# ospi152.net
KiCad netlist of a schematic drawn in EAGLE
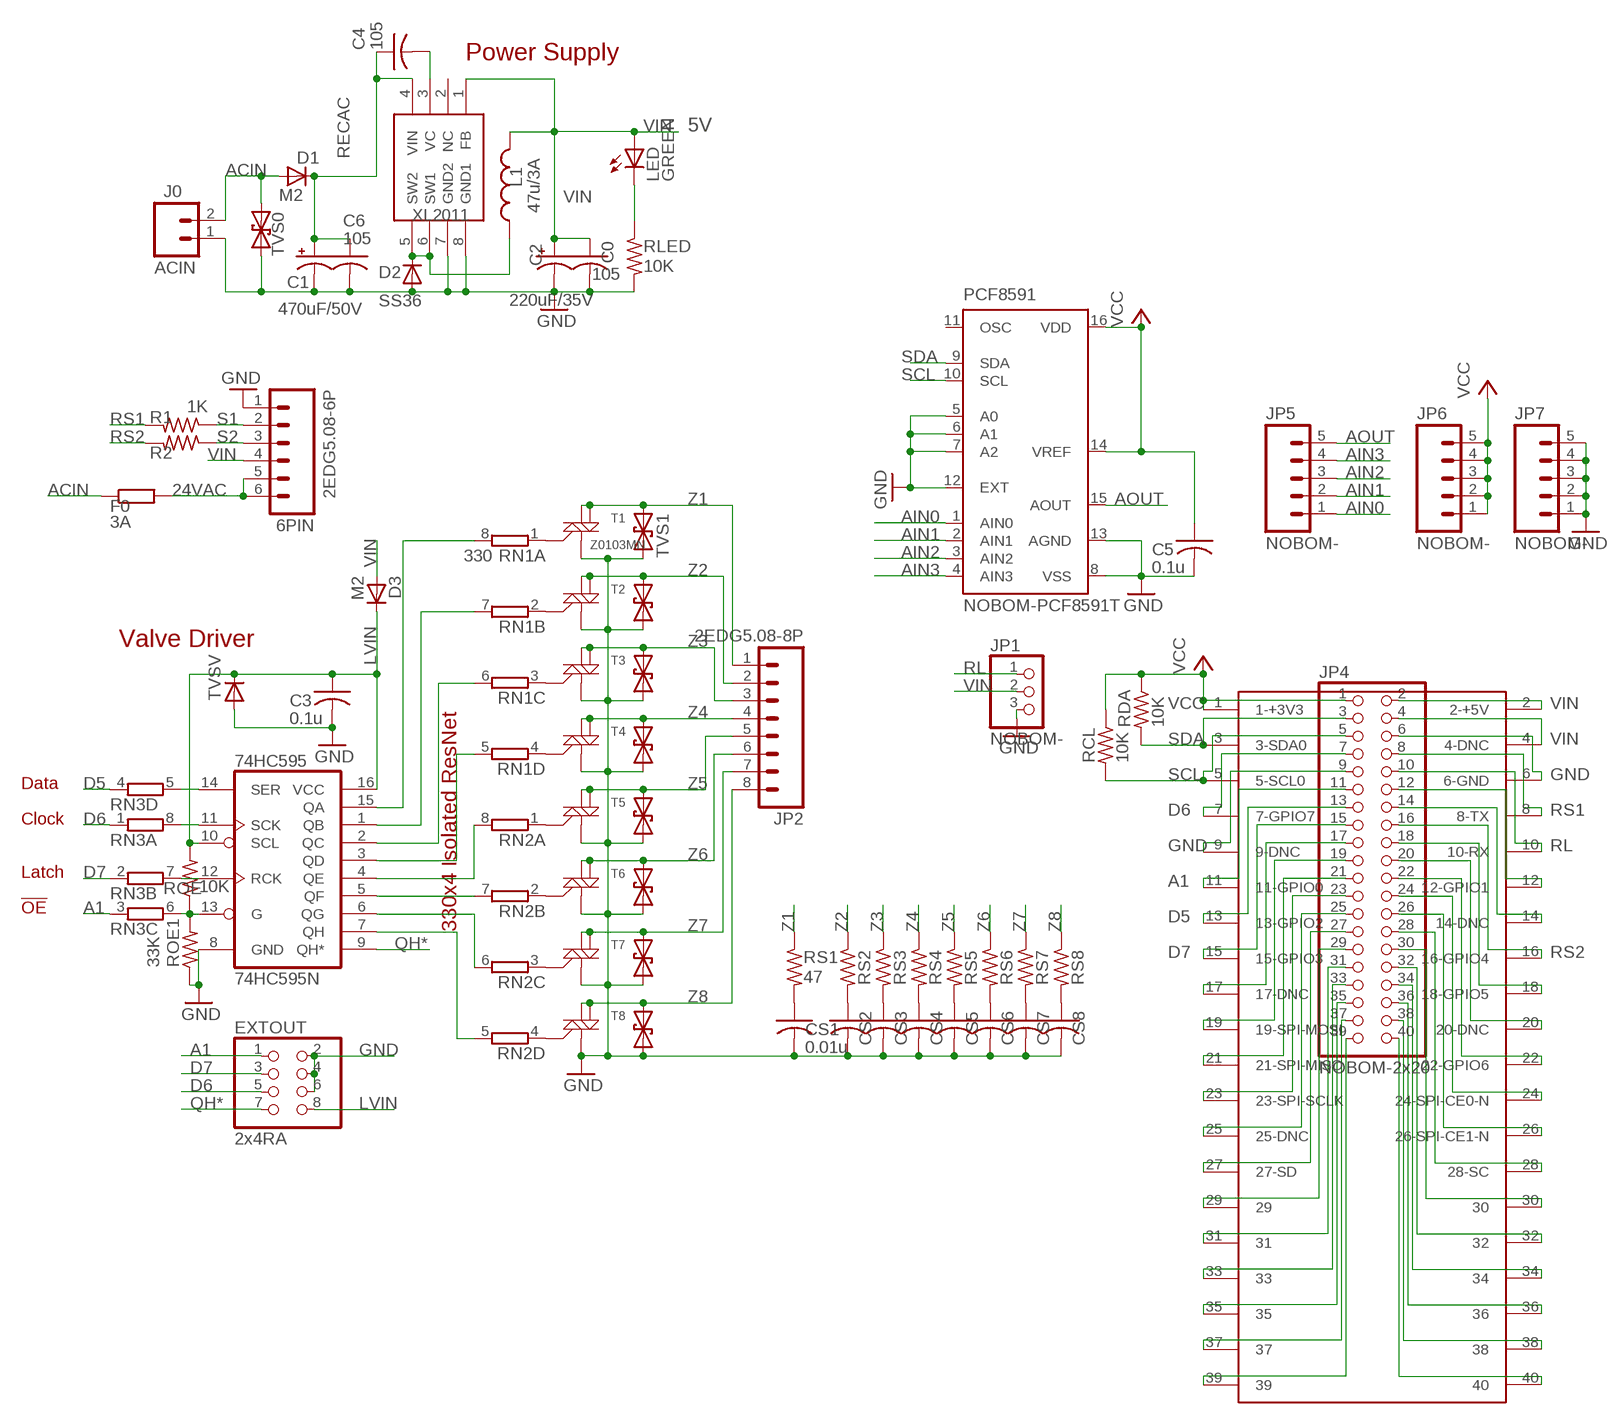
[diagram p0: schematic, sheet 1]

(export (version "E")
  (design (tool "Eeschema 10.0.6"))
  (components
    (comp (ref "6PIN")
      (value "2EDG5.08-6P")
      (footprint "eagle-import:SCREWTERMINAL-5MM-6")
      (libsource (lib "eagle-import") (part "M065MM"))
    )
    (comp (ref "74HC595")
      (value "74HC595N")
      (footprint "eagle-import:SO16")
      (libsource (lib "eagle-import") (part "74595DLS"))
    )
    (comp (ref "C0")
      (value "105")
      (footprint "eagle-import:C0603K")
      (libsource (lib "eagle-import") (part "C-USC0603K"))
    )
    (comp (ref "C1")
      (value "470uF/50V")
      (footprint "eagle-import:E5-10,5")
      (libsource (lib "eagle-import") (part "CPOL-USE5-10.5"))
    )
    (comp (ref "C2")
      (value "220uF/35V")
      (footprint "eagle-import:E3,5-8")
      (libsource (lib "eagle-import") (part "CPOL-USE3.5-8"))
    )
    (comp (ref "C3")
      (value "0.1u")
      (footprint "eagle-import:C0603K")
      (libsource (lib "eagle-import") (part "C-USC0603K"))
    )
    (comp (ref "C4")
      (value "105")
      (footprint "eagle-import:C0603K")
      (libsource (lib "eagle-import") (part "C-USC0603K"))
    )
    (comp (ref "C5")
      (value "0.1u")
      (footprint "eagle-import:C0603K")
      (libsource (lib "eagle-import") (part "C-USC0603K"))
    )
    (comp (ref "C6")
      (value "105")
      (footprint "eagle-import:C0603K")
      (libsource (lib "eagle-import") (part "C-USC0603K"))
    )
    (comp (ref "CS1")
      (value "0.01u")
      (footprint "eagle-import:C0603K")
      (libsource (lib "eagle-import") (part "C-USC0603K"))
    )
    (comp (ref "CS2")
      (value "0.01u")
      (footprint "eagle-import:C0603K")
      (libsource (lib "eagle-import") (part "C-USC0603K"))
    )
    (comp (ref "CS3")
      (value "0.01u")
      (footprint "eagle-import:C0603K")
      (libsource (lib "eagle-import") (part "C-USC0603K"))
    )
    (comp (ref "CS4")
      (value "0.01u")
      (footprint "eagle-import:C0603K")
      (libsource (lib "eagle-import") (part "C-USC0603K"))
    )
    (comp (ref "CS5")
      (value "0.01u")
      (footprint "eagle-import:C0603K")
      (libsource (lib "eagle-import") (part "C-USC0603K"))
    )
    (comp (ref "CS6")
      (value "0.01u")
      (footprint "eagle-import:C0603K")
      (libsource (lib "eagle-import") (part "C-USC0603K"))
    )
    (comp (ref "CS7")
      (value "0.01u")
      (footprint "eagle-import:C0603K")
      (libsource (lib "eagle-import") (part "C-USC0603K"))
    )
    (comp (ref "CS8")
      (value "0.01u")
      (footprint "eagle-import:C0603K")
      (libsource (lib "eagle-import") (part "C-USC0603K"))
    )
    (comp (ref "D1")
      (value "M2")
      (footprint "eagle-import:DO-214AC")
      (libsource (lib "eagle-import") (part "DIODE-DO-214AC"))
    )
    (comp (ref "D2")
      (value "SS36")
      (footprint "eagle-import:SMB")
      (libsource (lib "eagle-import") (part "DIODE-SMB"))
    )
    (comp (ref "D3")
      (value "M2")
      (footprint "eagle-import:DO-214AC")
      (libsource (lib "eagle-import") (part "DIODE-DO-214AC"))
    )
    (comp (ref "EXTOUT")
      (value "2x4RA")
      (footprint "eagle-import:2X04_90")
      (libsource (lib "eagle-import") (part "PINHD-2X4/90"))
    )
    (comp (ref "F0")
      (value "3A")
      (footprint "eagle-import:0207_15")
      (libsource (lib "eagle-import") (part "R-EU_0207/15"))
    )
    (comp (ref "J0")
      (value "ACIN")
      (footprint "eagle-import:SCREWTERMINAL-4MM-2-X")
      (libsource (lib "eagle-import") (part "M024MM-X"))
    )
    (comp (ref "JP1")
      (value "NOBOM-")
      (footprint "eagle-import:1X03")
      (libsource (lib "eagle-import") (part "PINHD-1X3"))
    )
    (comp (ref "JP2")
      (value "2EDG5.08-8P")
      (footprint "eagle-import:SCREWTERMINAL-5MM-8")
      (libsource (lib "eagle-import") (part "M085MM-8"))
    )
    (comp (ref "JP4")
      (value "NOBOM-2x20")
      (footprint "eagle-import:2X20")
      (libsource (lib "eagle-import") (part "PINHD-2X20"))
    )
    (comp (ref "JP5")
      (value "NOBOM-")
      (footprint "eagle-import:1X05")
      (libsource (lib "eagle-import") (part "M05PTH"))
    )
    (comp (ref "JP6")
      (value "NOBOM-")
      (footprint "eagle-import:1X05")
      (libsource (lib "eagle-import") (part "M05PTH"))
    )
    (comp (ref "JP7")
      (value "NOBOM-")
      (footprint "eagle-import:1X05")
      (libsource (lib "eagle-import") (part "M05PTH"))
    )
    (comp (ref "L1")
      (value "47u/3A")
      (footprint "eagle-import:YT1014")
      (libsource (lib "eagle-import") (part "INDUCTORYT1014"))
    )
    (comp (ref "LED")
      (value "GREEN")
      (footprint "eagle-import:CHIPLED_0805")
      (libsource (lib "eagle-import") (part "LEDCHIPLED_0805"))
    )
    (comp (ref "PCF8591")
      (value "NOBOM-PCF8591T")
      (footprint "eagle-import:SO16W")
      (fields (field (name "MPN") "PCF8591T/2,512"))
      (libsource (lib "eagle-import") (part "PCF8591T"))
    )
    (comp (ref "R1")
      (value "1K")
      (footprint "eagle-import:R0603")
      (libsource (lib "eagle-import") (part "R-US_R0603"))
    )
    (comp (ref "R2")
      (value "1K")
      (footprint "eagle-import:R0603")
      (libsource (lib "eagle-import") (part "R-US_R0603"))
    )
    (comp (ref "RCL")
      (value "10K")
      (footprint "eagle-import:R0603")
      (libsource (lib "eagle-import") (part "R-US_R0603"))
    )
    (comp (ref "RDA")
      (value "10K")
      (footprint "eagle-import:R0603")
      (libsource (lib "eagle-import") (part "R-US_R0603"))
    )
    (comp (ref "RLED")
      (value "10K")
      (footprint "eagle-import:R0603")
      (libsource (lib "eagle-import") (part "R-US_R0603"))
    )
    (comp (ref "RN1")
      (value "330")
      (footprint "eagle-import:EXB38V")
      (libsource (lib "eagle-import") (part "4R-NEXB38V"))
    )
    (comp (ref "RN2")
      (value "330")
      (footprint "eagle-import:EXB38V")
      (libsource (lib "eagle-import") (part "4R-NEXB38V"))
    )
    (comp (ref "RN3")
      (value "330")
      (footprint "eagle-import:EXB38V")
      (libsource (lib "eagle-import") (part "4R-NEXB38V"))
    )
    (comp (ref "ROE")
      (value "10K")
      (footprint "eagle-import:R0603")
      (libsource (lib "eagle-import") (part "R-US_R0603"))
    )
    (comp (ref "ROE1")
      (value "33K")
      (footprint "eagle-import:R0603")
      (libsource (lib "eagle-import") (part "R-US_R0603"))
    )
    (comp (ref "RPI")
      (value "RPIB+B+")
      (footprint "eagle-import:RPIB+")
      (libsource (lib "eagle-import") (part "RPIB+B+"))
    )
    (comp (ref "RS1")
      (value "47")
      (footprint "eagle-import:R0603")
      (libsource (lib "eagle-import") (part "R-US_R0603"))
    )
    (comp (ref "RS2")
      (value "47")
      (footprint "eagle-import:R0603")
      (libsource (lib "eagle-import") (part "R-US_R0603"))
    )
    (comp (ref "RS3")
      (value "47")
      (footprint "eagle-import:R0603")
      (libsource (lib "eagle-import") (part "R-US_R0603"))
    )
    (comp (ref "RS4")
      (value "47")
      (footprint "eagle-import:R0603")
      (libsource (lib "eagle-import") (part "R-US_R0603"))
    )
    (comp (ref "RS5")
      (value "47")
      (footprint "eagle-import:R0603")
      (libsource (lib "eagle-import") (part "R-US_R0603"))
    )
    (comp (ref "RS6")
      (value "47")
      (footprint "eagle-import:R0603")
      (libsource (lib "eagle-import") (part "R-US_R0603"))
    )
    (comp (ref "RS7")
      (value "47")
      (footprint "eagle-import:R0603")
      (libsource (lib "eagle-import") (part "R-US_R0603"))
    )
    (comp (ref "RS8")
      (value "47")
      (footprint "eagle-import:R0603")
      (libsource (lib "eagle-import") (part "R-US_R0603"))
    )
    (comp (ref "T1")
      (value "Z0103MN")
      (footprint "eagle-import:SOT223")
      (libsource (lib "eagle-import") (part "MAC97SOT223"))
    )
    (comp (ref "T2")
      (value "Z0103MN")
      (footprint "eagle-import:SOT223")
      (libsource (lib "eagle-import") (part "MAC97SOT223"))
    )
    (comp (ref "T3")
      (value "Z0103MN")
      (footprint "eagle-import:SOT223")
      (libsource (lib "eagle-import") (part "MAC97SOT223"))
    )
    (comp (ref "T4")
      (value "Z0103MN")
      (footprint "eagle-import:SOT223")
      (libsource (lib "eagle-import") (part "MAC97SOT223"))
    )
    (comp (ref "T5")
      (value "Z0103MN")
      (footprint "eagle-import:SOT223")
      (libsource (lib "eagle-import") (part "MAC97SOT223"))
    )
    (comp (ref "T6")
      (value "Z0103MN")
      (footprint "eagle-import:SOT223")
      (libsource (lib "eagle-import") (part "MAC97SOT223"))
    )
    (comp (ref "T7")
      (value "Z0103MN")
      (footprint "eagle-import:SOT223")
      (libsource (lib "eagle-import") (part "MAC97SOT223"))
    )
    (comp (ref "T8")
      (value "Z0103MN")
      (footprint "eagle-import:SOT223")
      (libsource (lib "eagle-import") (part "MAC97SOT223"))
    )
    (comp (ref "TVS0")
      (value "TVSSMB")
      (footprint "eagle-import:SMB")
      (libsource (lib "eagle-import") (part "TVSSMB"))
    )
    (comp (ref "TVS1")
      (value "SMBJ43CA")
      (footprint "eagle-import:SMB")
      (libsource (lib "eagle-import") (part "TVSSMB"))
    )
    (comp (ref "TVS2")
      (value "SMBJ43CA")
      (footprint "eagle-import:SMB")
      (libsource (lib "eagle-import") (part "TVSSMB"))
    )
    (comp (ref "TVS3")
      (value "SMBJ43CA")
      (footprint "eagle-import:SMB")
      (libsource (lib "eagle-import") (part "TVSSMB"))
    )
    (comp (ref "TVS4")
      (value "SMBJ43CA")
      (footprint "eagle-import:SMB")
      (libsource (lib "eagle-import") (part "TVSSMB"))
    )
    (comp (ref "TVS5")
      (value "SMBJ43CA")
      (footprint "eagle-import:SMB")
      (libsource (lib "eagle-import") (part "TVSSMB"))
    )
    (comp (ref "TVS6")
      (value "SMBJ43CA")
      (footprint "eagle-import:SMB")
      (libsource (lib "eagle-import") (part "TVSSMB"))
    )
    (comp (ref "TVS7")
      (value "SMBJ43CA")
      (footprint "eagle-import:SMB")
      (libsource (lib "eagle-import") (part "TVSSMB"))
    )
    (comp (ref "TVS8")
      (value "SMBJ43CA")
      (footprint "eagle-import:SMB")
      (libsource (lib "eagle-import") (part "TVSSMB"))
    )
    (comp (ref "TVSV")
      (value "SMBJ5.0A")
      (footprint "eagle-import:SMA-DIODE_ALT")
      (libsource (lib "eagle-import") (part "DIODESMA-ALT"))
    )
    (comp (ref "XL2011")
      (value "XL2011")
      (footprint "eagle-import:SO08")
      (libsource (lib "eagle-import") (part "XL2001"))
    )
  )
  (nets
    (net (code "1") (name "/24VAC") (class "Default")
      (node (ref "6PIN") (pin "5") (pinfunction "5_5") (pintype "passive"))
      (node (ref "6PIN") (pin "6") (pinfunction "6_6") (pintype "passive"))
      (node (ref "F0") (pin "2") (pinfunction "2_2") (pintype "passive"))
    )
    (net (code "2") (name "/A1") (class "Default")
      (node (ref "EXTOUT") (pin "1") (pinfunction "1_1") (pintype "passive"))
      (node (ref "JP4") (pin "11") (pinfunction "11_11") (pintype "passive"))
      (node (ref "RN3") (pin "3") (pinfunction "1_3") (pintype "passive"))
      (node (ref "RPI") (pin "11") (pinfunction "11-GPIO0_11") (pintype "bidirectional"))
    )
    (net (code "3") (name "/ACIN") (class "Default")
      (node (ref "D1") (pin "A") (pinfunction "A_A") (pintype "passive"))
      (node (ref "F0") (pin "1") (pinfunction "1_1") (pintype "passive"))
      (node (ref "J0") (pin "2") (pinfunction "2_2") (pintype "passive"))
      (node (ref "TVS0") (pin "C") (pinfunction "C_C") (pintype "passive"))
    )
    (net (code "4") (name "/AIN0") (class "Default")
      (node (ref "JP5") (pin "1") (pinfunction "1_1") (pintype "passive"))
      (node (ref "PCF8591") (pin "1") (pinfunction "AIN0_1") (pintype "input"))
    )
    (net (code "5") (name "/AIN1") (class "Default")
      (node (ref "JP5") (pin "2") (pinfunction "2_2") (pintype "passive"))
      (node (ref "PCF8591") (pin "2") (pinfunction "AIN1_2") (pintype "input"))
    )
    (net (code "6") (name "/AIN2") (class "Default")
      (node (ref "JP5") (pin "3") (pinfunction "3_3") (pintype "passive"))
      (node (ref "PCF8591") (pin "3") (pinfunction "AIN2_3") (pintype "input"))
    )
    (net (code "7") (name "/AIN3") (class "Default")
      (node (ref "JP5") (pin "4") (pinfunction "4_4") (pintype "passive"))
      (node (ref "PCF8591") (pin "4") (pinfunction "AIN3_4") (pintype "input"))
    )
    (net (code "8") (name "/AOUT") (class "Default")
      (node (ref "JP5") (pin "5") (pinfunction "5_5") (pintype "passive"))
      (node (ref "PCF8591") (pin "15") (pinfunction "AOUT_15") (pintype "output"))
    )
    (net (code "9") (name "/D5") (class "Default")
      (node (ref "JP4") (pin "13") (pinfunction "13_13") (pintype "passive"))
      (node (ref "RN3") (pin "4") (pinfunction "1_4") (pintype "passive"))
      (node (ref "RPI") (pin "13") (pinfunction "13-GPIO2_13") (pintype "bidirectional"))
    )
    (net (code "10") (name "/D6") (class "Default")
      (node (ref "EXTOUT") (pin "5") (pinfunction "5_5") (pintype "passive"))
      (node (ref "JP4") (pin "7") (pinfunction "7_7") (pintype "passive"))
      (node (ref "RN3") (pin "1") (pinfunction "1_1") (pintype "passive"))
      (node (ref "RPI") (pin "7") (pinfunction "7-GPIO7_7") (pintype "bidirectional"))
    )
    (net (code "11") (name "/D7") (class "Default")
      (node (ref "EXTOUT") (pin "3") (pinfunction "3_3") (pintype "passive"))
      (node (ref "JP4") (pin "15") (pinfunction "15_15") (pintype "passive"))
      (node (ref "RN3") (pin "2") (pinfunction "1_2") (pintype "passive"))
      (node (ref "RPI") (pin "15") (pinfunction "15-GPIO3_15") (pintype "bidirectional"))
    )
    (net (code "12") (name "/LVIN") (class "Default")
      (node (ref "74HC595") (pin "10") (pinfunction "SCL_10") (pintype "input"))
      (node (ref "74HC595") (pin "16") (pinfunction "VCC_16") (pintype "power_in"))
      (node (ref "C3") (pin "1") (pinfunction "1_1") (pintype "passive"))
      (node (ref "D3") (pin "C") (pinfunction "C_C") (pintype "passive"))
      (node (ref "EXTOUT") (pin "8") (pinfunction "8_8") (pintype "passive"))
      (node (ref "ROE") (pin "2") (pinfunction "2_2") (pintype "passive"))
      (node (ref "TVSV") (pin "C") (pinfunction "C_C") (pintype "passive"))
    )
    (net (code "13") (name "/QH*") (class "Default")
      (node (ref "74HC595") (pin "9") (pinfunction "QH*_9") (pintype "tri_state"))
      (node (ref "EXTOUT") (pin "7") (pinfunction "7_7") (pintype "passive"))
    )
    (net (code "14") (name "/RECAC") (class "Default")
      (node (ref "C1") (pin "+") (pinfunction "+_+") (pintype "passive"))
      (node (ref "C4") (pin "1") (pinfunction "1_1") (pintype "passive"))
      (node (ref "C6") (pin "1") (pinfunction "1_1") (pintype "passive"))
      (node (ref "D1") (pin "C") (pinfunction "C_C") (pintype "passive"))
      (node (ref "XL2011") (pin "4") (pinfunction "VIN_4") (pintype "bidirectional"))
    )
    (net (code "15") (name "/RL") (class "Default")
      (node (ref "JP1") (pin "1") (pinfunction "1_1") (pintype "passive"))
      (node (ref "JP4") (pin "10") (pinfunction "10_10") (pintype "passive"))
      (node (ref "RPI") (pin "10") (pinfunction "10-RX_10") (pintype "bidirectional"))
    )
    (net (code "16") (name "/RS1") (class "Default")
      (node (ref "JP4") (pin "8") (pinfunction "8_8") (pintype "passive"))
      (node (ref "R1") (pin "2") (pinfunction "2_2") (pintype "passive"))
      (node (ref "RPI") (pin "8") (pinfunction "8-TX_8") (pintype "bidirectional"))
    )
    (net (code "17") (name "/RS2") (class "Default")
      (node (ref "JP4") (pin "16") (pinfunction "16_16") (pintype "passive"))
      (node (ref "R2") (pin "2") (pinfunction "2_2") (pintype "passive"))
      (node (ref "RPI") (pin "16") (pinfunction "16-GPIO4_16") (pintype "bidirectional"))
    )
    (net (code "18") (name "/S1") (class "Default")
      (node (ref "6PIN") (pin "2") (pinfunction "2_2") (pintype "passive"))
      (node (ref "R1") (pin "1") (pinfunction "1_1") (pintype "passive"))
    )
    (net (code "19") (name "/S2") (class "Default")
      (node (ref "6PIN") (pin "3") (pinfunction "3_3") (pintype "passive"))
      (node (ref "R2") (pin "1") (pinfunction "1_1") (pintype "passive"))
    )
    (net (code "20") (name "/SCL") (class "Default")
      (node (ref "JP4") (pin "5") (pinfunction "5_5") (pintype "passive"))
      (node (ref "PCF8591") (pin "10") (pinfunction "SCL_10") (pintype "input"))
      (node (ref "RCL") (pin "2") (pinfunction "2_2") (pintype "passive"))
      (node (ref "RPI") (pin "5") (pinfunction "5-SCL0_5") (pintype "bidirectional"))
    )
    (net (code "21") (name "/SDA") (class "Default")
      (node (ref "JP4") (pin "3") (pinfunction "3_3") (pintype "passive"))
      (node (ref "PCF8591") (pin "9") (pinfunction "SDA_9") (pintype "bidirectional"))
      (node (ref "RDA") (pin "2") (pinfunction "2_2") (pintype "passive"))
      (node (ref "RPI") (pin "3") (pinfunction "3-SDA0_3") (pintype "bidirectional"))
    )
    (net (code "22") (name "/VIN") (class "Default")
      (node (ref "6PIN") (pin "4") (pinfunction "4_4") (pintype "passive"))
      (node (ref "C0") (pin "1") (pinfunction "1_1") (pintype "passive"))
      (node (ref "C2") (pin "+") (pinfunction "+_+") (pintype "passive"))
      (node (ref "D3") (pin "A") (pinfunction "A_A") (pintype "passive"))
      (node (ref "JP1") (pin "2") (pinfunction "2_2") (pintype "passive"))
      (node (ref "JP4") (pin "2") (pinfunction "2_2") (pintype "passive"))
      (node (ref "JP4") (pin "4") (pinfunction "4_4") (pintype "passive"))
      (node (ref "L1") (pin "P$2") (pinfunction "2_P$2") (pintype "passive"))
      (node (ref "LED") (pin "A") (pinfunction "A_A") (pintype "passive"))
      (node (ref "RPI") (pin "2") (pinfunction "2-+5V_2") (pintype "bidirectional"))
      (node (ref "RPI") (pin "4") (pinfunction "4-DNC_4") (pintype "bidirectional"))
      (node (ref "XL2011") (pin "1") (pinfunction "FB_1") (pintype "input"))
    )
    (net (code "23") (name "/Z1") (class "Default")
      (node (ref "JP2") (pin "1") (pinfunction "1_1") (pintype "passive"))
      (node (ref "RS1") (pin "1") (pinfunction "1_1") (pintype "passive"))
      (node (ref "T1") (pin "2") (pinfunction "M2_2") (pintype "bidirectional"))
      (node (ref "T1") (pin "4") (pinfunction "M2-4_4") (pintype "bidirectional"))
      (node (ref "TVS1") (pin "A") (pinfunction "A_A") (pintype "passive"))
    )
    (net (code "24") (name "/Z2") (class "Default")
      (node (ref "JP2") (pin "2") (pinfunction "2_2") (pintype "passive"))
      (node (ref "RS2") (pin "1") (pinfunction "1_1") (pintype "passive"))
      (node (ref "T2") (pin "2") (pinfunction "M2_2") (pintype "bidirectional"))
      (node (ref "T2") (pin "4") (pinfunction "M2-4_4") (pintype "bidirectional"))
      (node (ref "TVS2") (pin "A") (pinfunction "A_A") (pintype "passive"))
    )
    (net (code "25") (name "/Z3") (class "Default")
      (node (ref "JP2") (pin "3") (pinfunction "3_3") (pintype "passive"))
      (node (ref "RS3") (pin "1") (pinfunction "1_1") (pintype "passive"))
      (node (ref "T3") (pin "2") (pinfunction "M2_2") (pintype "bidirectional"))
      (node (ref "T3") (pin "4") (pinfunction "M2-4_4") (pintype "bidirectional"))
      (node (ref "TVS3") (pin "A") (pinfunction "A_A") (pintype "passive"))
    )
    (net (code "26") (name "/Z4") (class "Default")
      (node (ref "JP2") (pin "4") (pinfunction "4_4") (pintype "passive"))
      (node (ref "RS4") (pin "1") (pinfunction "1_1") (pintype "passive"))
      (node (ref "T4") (pin "2") (pinfunction "M2_2") (pintype "bidirectional"))
      (node (ref "T4") (pin "4") (pinfunction "M2-4_4") (pintype "bidirectional"))
      (node (ref "TVS4") (pin "A") (pinfunction "A_A") (pintype "passive"))
    )
    (net (code "27") (name "/Z5") (class "Default")
      (node (ref "JP2") (pin "5") (pinfunction "5_5") (pintype "passive"))
      (node (ref "RS5") (pin "1") (pinfunction "1_1") (pintype "passive"))
      (node (ref "T5") (pin "2") (pinfunction "M2_2") (pintype "bidirectional"))
      (node (ref "T5") (pin "4") (pinfunction "M2-4_4") (pintype "bidirectional"))
      (node (ref "TVS5") (pin "A") (pinfunction "A_A") (pintype "passive"))
    )
    (net (code "28") (name "/Z6") (class "Default")
      (node (ref "JP2") (pin "6") (pinfunction "6_6") (pintype "passive"))
      (node (ref "RS6") (pin "1") (pinfunction "1_1") (pintype "passive"))
      (node (ref "T6") (pin "2") (pinfunction "M2_2") (pintype "bidirectional"))
      (node (ref "T6") (pin "4") (pinfunction "M2-4_4") (pintype "bidirectional"))
      (node (ref "TVS6") (pin "A") (pinfunction "A_A") (pintype "passive"))
    )
    (net (code "29") (name "/Z7") (class "Default")
      (node (ref "JP2") (pin "7") (pinfunction "7_7") (pintype "passive"))
      (node (ref "RS7") (pin "1") (pinfunction "1_1") (pintype "passive"))
      (node (ref "T7") (pin "2") (pinfunction "M2_2") (pintype "bidirectional"))
      (node (ref "T7") (pin "4") (pinfunction "M2-4_4") (pintype "bidirectional"))
      (node (ref "TVS7") (pin "A") (pinfunction "A_A") (pintype "passive"))
    )
    (net (code "30") (name "/Z8") (class "Default")
      (node (ref "JP2") (pin "8") (pinfunction "8_8") (pintype "passive"))
      (node (ref "RS8") (pin "1") (pinfunction "1_1") (pintype "passive"))
      (node (ref "T8") (pin "2") (pinfunction "M2_2") (pintype "bidirectional"))
      (node (ref "T8") (pin "4") (pinfunction "M2-4_4") (pintype "bidirectional"))
      (node (ref "TVS8") (pin "A") (pinfunction "A_A") (pintype "passive"))
    )
    (net (code "31") (name "GND") (class "Default")
      (node (ref "6PIN") (pin "1") (pinfunction "1_1") (pintype "passive"))
      (node (ref "74HC595") (pin "8") (pinfunction "GND_8") (pintype "power_in"))
      (node (ref "C0") (pin "2") (pinfunction "2_2") (pintype "passive"))
      (node (ref "C1") (pin "-") (pinfunction "-_-") (pintype "passive"))
      (node (ref "C2") (pin "-") (pinfunction "-_-") (pintype "passive"))
      (node (ref "C3") (pin "2") (pinfunction "2_2") (pintype "passive"))
      (node (ref "C5") (pin "2") (pinfunction "2_2") (pintype "passive"))
      (node (ref "C6") (pin "2") (pinfunction "2_2") (pintype "passive"))
      (node (ref "CS1") (pin "2") (pinfunction "2_2") (pintype "passive"))
      (node (ref "CS2") (pin "2") (pinfunction "2_2") (pintype "passive"))
      (node (ref "CS3") (pin "2") (pinfunction "2_2") (pintype "passive"))
      (node (ref "CS4") (pin "2") (pinfunction "2_2") (pintype "passive"))
      (node (ref "CS5") (pin "2") (pinfunction "2_2") (pintype "passive"))
      (node (ref "CS6") (pin "2") (pinfunction "2_2") (pintype "passive"))
      (node (ref "CS7") (pin "2") (pinfunction "2_2") (pintype "passive"))
      (node (ref "CS8") (pin "2") (pinfunction "2_2") (pintype "passive"))
      (node (ref "D2") (pin "A") (pinfunction "A_A") (pintype "passive"))
      (node (ref "EXTOUT") (pin "2") (pinfunction "2_2") (pintype "passive"))
      (node (ref "EXTOUT") (pin "4") (pinfunction "4_4") (pintype "passive"))
      (node (ref "EXTOUT") (pin "6") (pinfunction "6_6") (pintype "passive"))
      (node (ref "J0") (pin "1") (pinfunction "1_1") (pintype "passive"))
      (node (ref "JP1") (pin "3") (pinfunction "3_3") (pintype "passive"))
      (node (ref "JP4") (pin "6") (pinfunction "6_6") (pintype "passive"))
      (node (ref "JP4") (pin "9") (pinfunction "9_9") (pintype "passive"))
      (node (ref "JP7") (pin "1") (pinfunction "1_1") (pintype "passive"))
      (node (ref "JP7") (pin "2") (pinfunction "2_2") (pintype "passive"))
      (node (ref "JP7") (pin "3") (pinfunction "3_3") (pintype "passive"))
      (node (ref "JP7") (pin "4") (pinfunction "4_4") (pintype "passive"))
      (node (ref "JP7") (pin "5") (pinfunction "5_5") (pintype "passive"))
      (node (ref "PCF8591") (pin "12") (pinfunction "EXT_12") (pintype "input"))
      (node (ref "PCF8591") (pin "13") (pinfunction "AGND_13") (pintype "power_in"))
      (node (ref "PCF8591") (pin "5") (pinfunction "A0_5") (pintype "input"))
      (node (ref "PCF8591") (pin "6") (pinfunction "A1_6") (pintype "input"))
      (node (ref "PCF8591") (pin "7") (pinfunction "A2_7") (pintype "input"))
      (node (ref "PCF8591") (pin "8") (pinfunction "VSS_8") (pintype "power_in"))
      (node (ref "RLED") (pin "2") (pinfunction "2_2") (pintype "passive"))
      (node (ref "ROE1") (pin "1") (pinfunction "1_1") (pintype "passive"))
      (node (ref "RPI") (pin "6") (pinfunction "6-GND_6") (pintype "bidirectional"))
      (node (ref "RPI") (pin "9") (pinfunction "9-DNC_9") (pintype "bidirectional"))
      (node (ref "T1") (pin "1") (pinfunction "M1_1") (pintype "bidirectional"))
      (node (ref "T2") (pin "1") (pinfunction "M1_1") (pintype "bidirectional"))
      (node (ref "T3") (pin "1") (pinfunction "M1_1") (pintype "bidirectional"))
      (node (ref "T4") (pin "1") (pinfunction "M1_1") (pintype "bidirectional"))
      (node (ref "T5") (pin "1") (pinfunction "M1_1") (pintype "bidirectional"))
      (node (ref "T6") (pin "1") (pinfunction "M1_1") (pintype "bidirectional"))
      (node (ref "T7") (pin "1") (pinfunction "M1_1") (pintype "bidirectional"))
      (node (ref "T8") (pin "1") (pinfunction "M1_1") (pintype "bidirectional"))
      (node (ref "TVS0") (pin "A") (pinfunction "A_A") (pintype "passive"))
      (node (ref "TVS1") (pin "C") (pinfunction "C_C") (pintype "passive"))
      (node (ref "TVS2") (pin "C") (pinfunction "C_C") (pintype "passive"))
      (node (ref "TVS3") (pin "C") (pinfunction "C_C") (pintype "passive"))
      (node (ref "TVS4") (pin "C") (pinfunction "C_C") (pintype "passive"))
      (node (ref "TVS5") (pin "C") (pinfunction "C_C") (pintype "passive"))
      (node (ref "TVS6") (pin "C") (pinfunction "C_C") (pintype "passive"))
      (node (ref "TVS7") (pin "C") (pinfunction "C_C") (pintype "passive"))
      (node (ref "TVS8") (pin "C") (pinfunction "C_C") (pintype "passive"))
      (node (ref "TVSV") (pin "A") (pinfunction "A_A") (pintype "passive"))
      (node (ref "XL2011") (pin "7") (pinfunction "GND2_7") (pintype "power_in"))
      (node (ref "XL2011") (pin "8") (pinfunction "GND1_8") (pintype "power_in"))
    )
    (net (code "32") (name "Net-(74HC595-G)") (class "Default")
      (node (ref "74HC595") (pin "13") (pinfunction "G_13") (pintype "input"))
      (node (ref "RN3") (pin "6") (pinfunction "2_6") (pintype "passive"))
      (node (ref "ROE") (pin "1") (pinfunction "1_1") (pintype "passive"))
      (node (ref "ROE1") (pin "2") (pinfunction "2_2") (pintype "passive"))
    )
    (net (code "33") (name "Net-(74HC595-QA)") (class "Default")
      (node (ref "74HC595") (pin "15") (pinfunction "QA_15") (pintype "tri_state"))
      (node (ref "RN1") (pin "8") (pinfunction "2_8") (pintype "passive"))
    )
    (net (code "34") (name "Net-(74HC595-QB)") (class "Default")
      (node (ref "74HC595") (pin "1") (pinfunction "QB_1") (pintype "tri_state"))
      (node (ref "RN1") (pin "7") (pinfunction "2_7") (pintype "passive"))
    )
    (net (code "35") (name "Net-(74HC595-QC)") (class "Default")
      (node (ref "74HC595") (pin "2") (pinfunction "QC_2") (pintype "tri_state"))
      (node (ref "RN1") (pin "6") (pinfunction "2_6") (pintype "passive"))
    )
    (net (code "36") (name "Net-(74HC595-QD)") (class "Default")
      (node (ref "74HC595") (pin "3") (pinfunction "QD_3") (pintype "tri_state"))
      (node (ref "RN1") (pin "5") (pinfunction "2_5") (pintype "passive"))
    )
    (net (code "37") (name "Net-(74HC595-QE)") (class "Default")
      (node (ref "74HC595") (pin "4") (pinfunction "QE_4") (pintype "tri_state"))
      (node (ref "RN2") (pin "8") (pinfunction "2_8") (pintype "passive"))
    )
    (net (code "38") (name "Net-(74HC595-QF)") (class "Default")
      (node (ref "74HC595") (pin "5") (pinfunction "QF_5") (pintype "tri_state"))
      (node (ref "RN2") (pin "7") (pinfunction "2_7") (pintype "passive"))
    )
    (net (code "39") (name "Net-(74HC595-QG)") (class "Default")
      (node (ref "74HC595") (pin "6") (pinfunction "QG_6") (pintype "tri_state"))
      (node (ref "RN2") (pin "6") (pinfunction "2_6") (pintype "passive"))
    )
    (net (code "40") (name "Net-(74HC595-QH)") (class "Default")
      (node (ref "74HC595") (pin "7") (pinfunction "QH_7") (pintype "tri_state"))
      (node (ref "RN2") (pin "5") (pinfunction "2_5") (pintype "passive"))
    )
    (net (code "41") (name "Net-(74HC595-RCK)") (class "Default")
      (node (ref "74HC595") (pin "12") (pinfunction "RCK_12") (pintype "input"))
      (node (ref "RN3") (pin "7") (pinfunction "2_7") (pintype "passive"))
    )
    (net (code "42") (name "Net-(74HC595-SCK)") (class "Default")
      (node (ref "74HC595") (pin "11") (pinfunction "SCK_11") (pintype "input"))
      (node (ref "RN3") (pin "8") (pinfunction "2_8") (pintype "passive"))
    )
    (net (code "43") (name "Net-(74HC595-SER)") (class "Default")
      (node (ref "74HC595") (pin "14") (pinfunction "SER_14") (pintype "input"))
      (node (ref "RN3") (pin "5") (pinfunction "2_5") (pintype "passive"))
    )
    (net (code "44") (name "Net-(CS1-Pad1)") (class "Default")
      (node (ref "CS1") (pin "1") (pinfunction "1_1") (pintype "passive"))
      (node (ref "RS1") (pin "2") (pinfunction "2_2") (pintype "passive"))
    )
    (net (code "45") (name "Net-(CS2-Pad1)") (class "Default")
      (node (ref "CS2") (pin "1") (pinfunction "1_1") (pintype "passive"))
      (node (ref "RS2") (pin "2") (pinfunction "2_2") (pintype "passive"))
    )
    (net (code "46") (name "Net-(CS3-Pad1)") (class "Default")
      (node (ref "CS3") (pin "1") (pinfunction "1_1") (pintype "passive"))
      (node (ref "RS3") (pin "2") (pinfunction "2_2") (pintype "passive"))
    )
    (net (code "47") (name "Net-(CS4-Pad1)") (class "Default")
      (node (ref "CS4") (pin "1") (pinfunction "1_1") (pintype "passive"))
      (node (ref "RS4") (pin "2") (pinfunction "2_2") (pintype "passive"))
    )
    (net (code "48") (name "Net-(CS5-Pad1)") (class "Default")
      (node (ref "CS5") (pin "1") (pinfunction "1_1") (pintype "passive"))
      (node (ref "RS5") (pin "2") (pinfunction "2_2") (pintype "passive"))
    )
    (net (code "49") (name "Net-(CS6-Pad1)") (class "Default")
      (node (ref "CS6") (pin "1") (pinfunction "1_1") (pintype "passive"))
      (node (ref "RS6") (pin "2") (pinfunction "2_2") (pintype "passive"))
    )
    (net (code "50") (name "Net-(CS7-Pad1)") (class "Default")
      (node (ref "CS7") (pin "1") (pinfunction "1_1") (pintype "passive"))
      (node (ref "RS7") (pin "2") (pinfunction "2_2") (pintype "passive"))
    )
    (net (code "51") (name "Net-(CS8-Pad1)") (class "Default")
      (node (ref "CS8") (pin "1") (pinfunction "1_1") (pintype "passive"))
      (node (ref "RS8") (pin "2") (pinfunction "2_2") (pintype "passive"))
    )
    (net (code "52") (name "Net-(JP4-Pad29)") (class "Default")
      (node (ref "JP4") (pin "29") (pinfunction "29_29") (pintype "passive"))
      (node (ref "RPI") (pin "29") (pinfunction "29_29") (pintype "bidirectional"))
    )
    (net (code "53") (name "Net-(JP4-Pad30)") (class "Default")
      (node (ref "JP4") (pin "30") (pinfunction "30_30") (pintype "passive"))
      (node (ref "RPI") (pin "30") (pinfunction "30_30") (pintype "bidirectional"))
    )
    (net (code "54") (name "Net-(JP4-Pad31)") (class "Default")
      (node (ref "JP4") (pin "31") (pinfunction "31_31") (pintype "passive"))
      (node (ref "RPI") (pin "31") (pinfunction "31_31") (pintype "bidirectional"))
    )
    (net (code "55") (name "Net-(JP4-Pad32)") (class "Default")
      (node (ref "JP4") (pin "32") (pinfunction "32_32") (pintype "passive"))
      (node (ref "RPI") (pin "32") (pinfunction "32_32") (pintype "bidirectional"))
    )
    (net (code "56") (name "Net-(JP4-Pad33)") (class "Default")
      (node (ref "JP4") (pin "33") (pinfunction "33_33") (pintype "passive"))
      (node (ref "RPI") (pin "33") (pinfunction "33_33") (pintype "bidirectional"))
    )
    (net (code "57") (name "Net-(JP4-Pad34)") (class "Default")
      (node (ref "JP4") (pin "34") (pinfunction "34_34") (pintype "passive"))
      (node (ref "RPI") (pin "34") (pinfunction "34_34") (pintype "bidirectional"))
    )
    (net (code "58") (name "Net-(JP4-Pad35)") (class "Default")
      (node (ref "JP4") (pin "35") (pinfunction "35_35") (pintype "passive"))
      (node (ref "RPI") (pin "35") (pinfunction "35_35") (pintype "bidirectional"))
    )
    (net (code "59") (name "Net-(JP4-Pad36)") (class "Default")
      (node (ref "JP4") (pin "36") (pinfunction "36_36") (pintype "passive"))
      (node (ref "RPI") (pin "36") (pinfunction "36_36") (pintype "bidirectional"))
    )
    (net (code "60") (name "Net-(JP4-Pad37)") (class "Default")
      (node (ref "JP4") (pin "37") (pinfunction "37_37") (pintype "passive"))
      (node (ref "RPI") (pin "37") (pinfunction "37_37") (pintype "bidirectional"))
    )
    (net (code "61") (name "Net-(JP4-Pad38)") (class "Default")
      (node (ref "JP4") (pin "38") (pinfunction "38_38") (pintype "passive"))
      (node (ref "RPI") (pin "38") (pinfunction "38_38") (pintype "bidirectional"))
    )
    (net (code "62") (name "Net-(JP4-Pad39)") (class "Default")
      (node (ref "JP4") (pin "39") (pinfunction "39_39") (pintype "passive"))
      (node (ref "RPI") (pin "39") (pinfunction "39_39") (pintype "bidirectional"))
    )
    (net (code "63") (name "Net-(JP4-Pad40)") (class "Default")
      (node (ref "JP4") (pin "40") (pinfunction "40_40") (pintype "passive"))
      (node (ref "RPI") (pin "40") (pinfunction "40_40") (pintype "bidirectional"))
    )
    (net (code "64") (name "Net-(L1-1)") (class "Default")
      (node (ref "D2") (pin "C") (pinfunction "C_C") (pintype "passive"))
      (node (ref "L1") (pin "P$1") (pinfunction "1_P$1") (pintype "passive"))
      (node (ref "XL2011") (pin "5") (pinfunction "SW2_5") (pintype "power_in"))
      (node (ref "XL2011") (pin "6") (pinfunction "SW1_6") (pintype "power_in"))
    )
    (net (code "65") (name "Net-(LED-PadC)") (class "Default")
      (node (ref "LED") (pin "C") (pinfunction "C_C") (pintype "passive"))
      (node (ref "RLED") (pin "1") (pinfunction "1_1") (pintype "passive"))
    )
    (net (code "66") (name "Net-(RN1B-1)") (class "Default")
      (node (ref "RN1") (pin "2") (pinfunction "1_2") (pintype "passive"))
      (node (ref "T2") (pin "3") (pinfunction "G_3") (pintype "bidirectional"))
    )
    (net (code "67") (name "Net-(RN1C-1)") (class "Default")
      (node (ref "RN1") (pin "3") (pinfunction "1_3") (pintype "passive"))
      (node (ref "T3") (pin "3") (pinfunction "G_3") (pintype "bidirectional"))
    )
    (net (code "68") (name "Net-(RN1D-1)") (class "Default")
      (node (ref "RN1") (pin "4") (pinfunction "1_4") (pintype "passive"))
      (node (ref "T4") (pin "3") (pinfunction "G_3") (pintype "bidirectional"))
    )
    (net (code "69") (name "Net-(RN2B-1)") (class "Default")
      (node (ref "RN2") (pin "2") (pinfunction "1_2") (pintype "passive"))
      (node (ref "T6") (pin "3") (pinfunction "G_3") (pintype "bidirectional"))
    )
    (net (code "70") (name "Net-(RN2C-1)") (class "Default")
      (node (ref "RN2") (pin "3") (pinfunction "1_3") (pintype "passive"))
      (node (ref "T7") (pin "3") (pinfunction "G_3") (pintype "bidirectional"))
    )
    (net (code "71") (name "Net-(RN2D-1)") (class "Default")
      (node (ref "RN2") (pin "4") (pinfunction "1_4") (pintype "passive"))
      (node (ref "T8") (pin "3") (pinfunction "G_3") (pintype "bidirectional"))
    )
    (net (code "72") (name "Net-(RPI-12-GPIO1)") (class "Default")
      (node (ref "JP4") (pin "12") (pinfunction "12_12") (pintype "passive"))
      (node (ref "RPI") (pin "12") (pinfunction "12-GPIO1_12") (pintype "bidirectional"))
    )
    (net (code "73") (name "Net-(RPI-14-DNC)") (class "Default")
      (node (ref "JP4") (pin "14") (pinfunction "14_14") (pintype "passive"))
      (node (ref "RPI") (pin "14") (pinfunction "14-DNC_14") (pintype "bidirectional"))
    )
    (net (code "74") (name "Net-(RPI-17-DNC)") (class "Default")
      (node (ref "JP4") (pin "17") (pinfunction "17_17") (pintype "passive"))
      (node (ref "RPI") (pin "17") (pinfunction "17-DNC_17") (pintype "bidirectional"))
    )
    (net (code "75") (name "Net-(RPI-18-GPIO5)") (class "Default")
      (node (ref "JP4") (pin "18") (pinfunction "18_18") (pintype "passive"))
      (node (ref "RPI") (pin "18") (pinfunction "18-GPIO5_18") (pintype "bidirectional"))
    )
    (net (code "76") (name "Net-(RPI-19-SPI-MOSI)") (class "Default")
      (node (ref "JP4") (pin "19") (pinfunction "19_19") (pintype "passive"))
      (node (ref "RPI") (pin "19") (pinfunction "19-SPI-MOSI_19") (pintype "bidirectional"))
    )
    (net (code "77") (name "Net-(RPI-20-DNC)") (class "Default")
      (node (ref "JP4") (pin "20") (pinfunction "20_20") (pintype "passive"))
      (node (ref "RPI") (pin "20") (pinfunction "20-DNC_20") (pintype "bidirectional"))
    )
    (net (code "78") (name "Net-(RPI-21-SPI-MISO)") (class "Default")
      (node (ref "JP4") (pin "21") (pinfunction "21_21") (pintype "passive"))
      (node (ref "RPI") (pin "21") (pinfunction "21-SPI-MISO_21") (pintype "bidirectional"))
    )
    (net (code "79") (name "Net-(RPI-22-GPIO6)") (class "Default")
      (node (ref "JP4") (pin "22") (pinfunction "22_22") (pintype "passive"))
      (node (ref "RPI") (pin "22") (pinfunction "22-GPIO6_22") (pintype "bidirectional"))
    )
    (net (code "80") (name "Net-(RPI-23-SPI-SCLK)") (class "Default")
      (node (ref "JP4") (pin "23") (pinfunction "23_23") (pintype "passive"))
      (node (ref "RPI") (pin "23") (pinfunction "23-SPI-SCLK_23") (pintype "bidirectional"))
    )
    (net (code "81") (name "Net-(RPI-24-SPI-CE0-N)") (class "Default")
      (node (ref "JP4") (pin "24") (pinfunction "24_24") (pintype "passive"))
      (node (ref "RPI") (pin "24") (pinfunction "24-SPI-CE0-N_24") (pintype "bidirectional"))
    )
    (net (code "82") (name "Net-(RPI-25-DNC)") (class "Default")
      (node (ref "JP4") (pin "25") (pinfunction "25_25") (pintype "passive"))
      (node (ref "RPI") (pin "25") (pinfunction "25-DNC_25") (pintype "bidirectional"))
    )
    (net (code "83") (name "Net-(RPI-26-SPI-CE1-N)") (class "Default")
      (node (ref "JP4") (pin "26") (pinfunction "26_26") (pintype "passive"))
      (node (ref "RPI") (pin "26") (pinfunction "26-SPI-CE1-N_26") (pintype "bidirectional"))
    )
    (net (code "84") (name "Net-(RPI-27-SD)") (class "Default")
      (node (ref "JP4") (pin "27") (pinfunction "27_27") (pintype "passive"))
      (node (ref "RPI") (pin "27") (pinfunction "27-SD_27") (pintype "bidirectional"))
    )
    (net (code "85") (name "Net-(RPI-28-SC)") (class "Default")
      (node (ref "JP4") (pin "28") (pinfunction "28_28") (pintype "passive"))
      (node (ref "RPI") (pin "28") (pinfunction "28-SC_28") (pintype "bidirectional"))
    )
    (net (code "86") (name "Net-(T1-G)") (class "Default")
      (node (ref "RN1") (pin "1") (pinfunction "1_1") (pintype "passive"))
      (node (ref "T1") (pin "3") (pinfunction "G_3") (pintype "bidirectional"))
    )
    (net (code "87") (name "Net-(T5-G)") (class "Default")
      (node (ref "RN2") (pin "1") (pinfunction "1_1") (pintype "passive"))
      (node (ref "T5") (pin "3") (pinfunction "G_3") (pintype "bidirectional"))
    )
    (net (code "88") (name "Net-(XL2011-VC)") (class "Default")
      (node (ref "C4") (pin "2") (pinfunction "2_2") (pintype "passive"))
      (node (ref "XL2011") (pin "3") (pinfunction "VC_3") (pintype "input"))
    )
    (net (code "89") (name "VCC") (class "Default")
      (node (ref "C5") (pin "1") (pinfunction "1_1") (pintype "passive"))
      (node (ref "JP4") (pin "1") (pinfunction "1_1") (pintype "passive"))
      (node (ref "JP6") (pin "1") (pinfunction "1_1") (pintype "passive"))
      (node (ref "JP6") (pin "2") (pinfunction "2_2") (pintype "passive"))
      (node (ref "JP6") (pin "3") (pinfunction "3_3") (pintype "passive"))
      (node (ref "JP6") (pin "4") (pinfunction "4_4") (pintype "passive"))
      (node (ref "JP6") (pin "5") (pinfunction "5_5") (pintype "passive"))
      (node (ref "PCF8591") (pin "14") (pinfunction "VREF_14") (pintype "input"))
      (node (ref "PCF8591") (pin "16") (pinfunction "VDD_16") (pintype "power_in"))
      (node (ref "RCL") (pin "1") (pinfunction "1_1") (pintype "passive"))
      (node (ref "RDA") (pin "1") (pinfunction "1_1") (pintype "passive"))
      (node (ref "RPI") (pin "1") (pinfunction "1-+3V3_1") (pintype "bidirectional"))
    )
    (net (code "90") (name "unconnected-(PCF8591-OSC-Pad11)") (class "Default")
      (node (ref "PCF8591") (pin "11") (pinfunction "OSC_11") (pintype "input"))
    )
    (net (code "91") (name "unconnected-(XL2011-NC-Pad2)") (class "Default")
      (node (ref "XL2011") (pin "2") (pinfunction "NC_2") (pintype "input"))
    )
  )
)
